# GPS-speed.net
KiCad netlist of a schematic drawn in Altium Designer
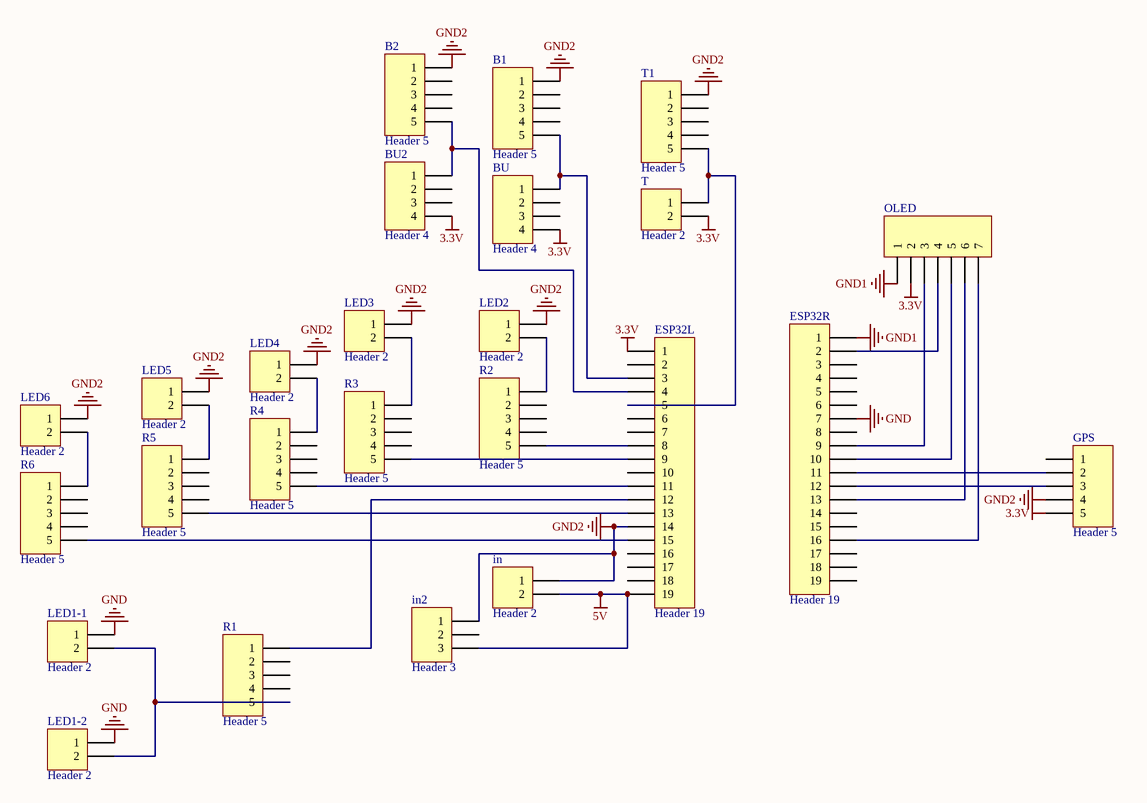
[diagram p0: GPS-speed.SchDoc]

(export (version "E")
  (design (tool "Eeschema 10.0.6"))
  (components
    (comp (ref "B1")
      (value "Header 5")
      (footprint "HDR1X5")
      (description "Header, 5-Pin")
      (fields (field (name "PUBLISHER") "Altium Limited"))
      (libsource (lib "Miscellaneous Connectors") (part "Header 5"))
    )
    (comp (ref "B2")
      (value "Header 5")
      (footprint "HDR1X5")
      (description "Header, 5-Pin")
      (fields (field (name "PUBLISHER") "Altium Limited"))
      (libsource (lib "Miscellaneous Connectors") (part "Header 5"))
    )
    (comp (ref "BU")
      (value "Header 4")
      (footprint "HDR1X4")
      (description "Header, 4-Pin")
      (fields (field (name "PUBLISHER") "Altium Limited"))
      (libsource (lib "Miscellaneous Connectors") (part "Header 4"))
    )
    (comp (ref "BU2")
      (value "Header 4")
      (footprint "HDR1X4")
      (description "Header, 4-Pin")
      (fields (field (name "PUBLISHER") "Altium Limited"))
      (libsource (lib "Miscellaneous Connectors") (part "Header 4"))
    )
    (comp (ref "ESP32L")
      (value "Header 19")
      (footprint "HDR1X19")
      (description "Header, 19-Pin")
      (fields (field (name "PUBLISHER") "Altium Limited"))
      (libsource (lib "") (part "Header 19_1"))
    )
    (comp (ref "ESP32R")
      (value "Header 19")
      (footprint "HDR1X19")
      (description "Header, 19-Pin")
      (fields (field (name "PUBLISHER") "Altium Limited"))
      (libsource (lib "Miscellaneous Connectors") (part "Header 19"))
    )
    (comp (ref "GPS")
      (value "Header 5")
      (footprint "HDR1X5")
      (description "Header, 5-Pin")
      (fields (field (name "PUBLISHER") "Altium Limited"))
      (libsource (lib "") (part "Header 5_1"))
    )
    (comp (ref "in")
      (value "Header 2")
      (footprint "HDR1X2")
      (description "Header, 2-Pin")
      (fields (field (name "PUBLISHER") "Altium Limited"))
      (libsource (lib "Miscellaneous Connectors") (part "Header 2"))
    )
    (comp (ref "in2")
      (value "Header 3")
      (footprint "HDR1X3")
      (description "Header, 3-Pin")
      (fields (field (name "PUBLISHER") "Altium Limited"))
      (libsource (lib "Miscellaneous Connectors") (part "Header 3"))
    )
    (comp (ref "LED1-1")
      (value "Header 2")
      (footprint "HDR1X2")
      (description "Header, 2-Pin")
      (fields (field (name "PUBLISHER") "Altium Limited"))
      (libsource (lib "Miscellaneous Connectors") (part "Header 2"))
    )
    (comp (ref "LED1-2")
      (value "Header 2")
      (footprint "HDR1X2")
      (description "Header, 2-Pin")
      (fields (field (name "PUBLISHER") "Altium Limited"))
      (libsource (lib "Miscellaneous Connectors") (part "Header 2"))
    )
    (comp (ref "LED2")
      (value "Header 2")
      (footprint "HDR1X2")
      (description "Header, 2-Pin")
      (fields (field (name "PUBLISHER") "Altium Limited"))
      (libsource (lib "Miscellaneous Connectors") (part "Header 2"))
    )
    (comp (ref "LED3")
      (value "Header 2")
      (footprint "HDR1X2")
      (description "Header, 2-Pin")
      (fields (field (name "PUBLISHER") "Altium Limited"))
      (libsource (lib "Miscellaneous Connectors") (part "Header 2"))
    )
    (comp (ref "LED4")
      (value "Header 2")
      (footprint "HDR1X2")
      (description "Header, 2-Pin")
      (fields (field (name "PUBLISHER") "Altium Limited"))
      (libsource (lib "Miscellaneous Connectors") (part "Header 2"))
    )
    (comp (ref "LED5")
      (value "Header 2")
      (footprint "HDR1X2")
      (description "Header, 2-Pin")
      (fields (field (name "PUBLISHER") "Altium Limited"))
      (libsource (lib "Miscellaneous Connectors") (part "Header 2"))
    )
    (comp (ref "LED6")
      (value "Header 2")
      (footprint "HDR1X2")
      (description "Header, 2-Pin")
      (fields (field (name "PUBLISHER") "Altium Limited"))
      (libsource (lib "Miscellaneous Connectors") (part "Header 2"))
    )
    (comp (ref "OLED")
      (value "Header 7")
      (footprint "HDR1X7")
      (description "Header, 7-Pin")
      (fields (field (name "PUBLISHER") "Altium Limited"))
      (libsource (lib "Miscellaneous Connectors") (part "Header 7"))
    )
    (comp (ref "R1")
      (value "Header 5")
      (footprint "HDR1X5")
      (description "Header, 5-Pin")
      (fields (field (name "PUBLISHER") "Altium Limited"))
      (libsource (lib "Miscellaneous Connectors") (part "Header 5"))
    )
    (comp (ref "R2")
      (value "Header 5")
      (footprint "HDR1X5")
      (description "Header, 5-Pin")
      (fields (field (name "PUBLISHER") "Altium Limited"))
      (libsource (lib "Miscellaneous Connectors") (part "Header 5"))
    )
    (comp (ref "R3")
      (value "Header 5")
      (footprint "HDR1X5")
      (description "Header, 5-Pin")
      (fields (field (name "PUBLISHER") "Altium Limited"))
      (libsource (lib "Miscellaneous Connectors") (part "Header 5"))
    )
    (comp (ref "R4")
      (value "Header 5")
      (footprint "HDR1X5")
      (description "Header, 5-Pin")
      (fields (field (name "PUBLISHER") "Altium Limited"))
      (libsource (lib "Miscellaneous Connectors") (part "Header 5"))
    )
    (comp (ref "R5")
      (value "Header 5")
      (footprint "HDR1X5")
      (description "Header, 5-Pin")
      (fields (field (name "PUBLISHER") "Altium Limited"))
      (libsource (lib "Miscellaneous Connectors") (part "Header 5"))
    )
    (comp (ref "R6")
      (value "Header 5")
      (footprint "HDR1X5")
      (description "Header, 5-Pin")
      (fields (field (name "PUBLISHER") "Altium Limited"))
      (libsource (lib "Miscellaneous Connectors") (part "Header 5"))
    )
    (comp (ref "T")
      (value "Header 2")
      (footprint "HDR1X2")
      (description "Header, 2-Pin")
      (fields (field (name "PUBLISHER") "Altium Limited"))
      (libsource (lib "Miscellaneous Connectors") (part "Header 2"))
    )
    (comp (ref "T1")
      (value "Header 5")
      (footprint "HDR1X5")
      (description "Header, 5-Pin")
      (fields (field (name "PUBLISHER") "Altium Limited"))
      (libsource (lib "Miscellaneous Connectors") (part "Header 5"))
    )
  )
  (nets
    (net (code "1") (name "3.3V") (class "Default")
      (node (ref "BU") (pin "4") (pinfunction "4_4") (pintype "passive"))
      (node (ref "BU2") (pin "4") (pinfunction "4_4") (pintype "passive"))
      (node (ref "ESP32L") (pin "1") (pinfunction "1_1") (pintype "passive"))
      (node (ref "GPS") (pin "5") (pinfunction "5_5") (pintype "passive"))
      (node (ref "OLED") (pin "2") (pinfunction "2_2") (pintype "passive"))
      (node (ref "T") (pin "2") (pinfunction "2_2") (pintype "passive"))
    )
    (net (code "2") (name "5V") (class "Default")
      (node (ref "ESP32L") (pin "19") (pinfunction "19_19") (pintype "passive"))
      (node (ref "in") (pin "2") (pinfunction "2_2") (pintype "passive"))
      (node (ref "in2") (pin "3") (pinfunction "3_3") (pintype "passive"))
    )
    (net (code "3") (name "GND") (class "Default")
      (node (ref "ESP32R") (pin "7") (pinfunction "7_7") (pintype "passive"))
      (node (ref "LED1-1") (pin "1") (pinfunction "1_1") (pintype "passive"))
      (node (ref "LED1-2") (pin "1") (pinfunction "1_1") (pintype "passive"))
    )
    (net (code "4") (name "GND1") (class "Default")
      (node (ref "ESP32R") (pin "1") (pinfunction "1_1") (pintype "passive"))
      (node (ref "OLED") (pin "1") (pinfunction "1_1") (pintype "passive"))
    )
    (net (code "5") (name "GND2") (class "Default")
      (node (ref "B1") (pin "1") (pinfunction "1_1") (pintype "passive"))
      (node (ref "B2") (pin "1") (pinfunction "1_1") (pintype "passive"))
      (node (ref "ESP32L") (pin "14") (pinfunction "14_14") (pintype "passive"))
      (node (ref "GPS") (pin "4") (pinfunction "4_4") (pintype "passive"))
      (node (ref "LED2") (pin "1") (pinfunction "1_1") (pintype "passive"))
      (node (ref "LED3") (pin "1") (pinfunction "1_1") (pintype "passive"))
      (node (ref "LED4") (pin "1") (pinfunction "1_1") (pintype "passive"))
      (node (ref "LED5") (pin "1") (pinfunction "1_1") (pintype "passive"))
      (node (ref "LED6") (pin "1") (pinfunction "1_1") (pintype "passive"))
      (node (ref "T1") (pin "1") (pinfunction "1_1") (pintype "passive"))
      (node (ref "in") (pin "1") (pinfunction "1_1") (pintype "passive"))
      (node (ref "in2") (pin "1") (pinfunction "1_1") (pintype "passive"))
    )
    (net (code "6") (name "Net-(B1-Pad5)") (class "Default")
      (node (ref "B1") (pin "5") (pinfunction "5_5") (pintype "passive"))
      (node (ref "BU") (pin "1") (pinfunction "1_1") (pintype "passive"))
      (node (ref "ESP32L") (pin "3") (pinfunction "3_3") (pintype "passive"))
    )
    (net (code "7") (name "Net-(B2-Pad5)") (class "Default")
      (node (ref "B2") (pin "5") (pinfunction "5_5") (pintype "passive"))
      (node (ref "BU2") (pin "1") (pinfunction "1_1") (pintype "passive"))
      (node (ref "ESP32L") (pin "4") (pinfunction "4_4") (pintype "passive"))
    )
    (net (code "8") (name "Net-(ESP32L-Pad5)") (class "Default")
      (node (ref "ESP32L") (pin "5") (pinfunction "5_5") (pintype "passive"))
      (node (ref "T") (pin "1") (pinfunction "1_1") (pintype "passive"))
      (node (ref "T1") (pin "5") (pinfunction "5_5") (pintype "passive"))
    )
    (net (code "9") (name "Net-(ESP32L-Pad8)") (class "Default")
      (node (ref "ESP32L") (pin "8") (pinfunction "8_8") (pintype "passive"))
      (node (ref "R2") (pin "5") (pinfunction "5_5") (pintype "passive"))
    )
    (net (code "10") (name "Net-(ESP32L-Pad9)") (class "Default")
      (node (ref "ESP32L") (pin "9") (pinfunction "9_9") (pintype "passive"))
      (node (ref "R3") (pin "5") (pinfunction "5_5") (pintype "passive"))
    )
    (net (code "11") (name "Net-(ESP32L-Pad11)") (class "Default")
      (node (ref "ESP32L") (pin "11") (pinfunction "11_11") (pintype "passive"))
      (node (ref "R4") (pin "5") (pinfunction "5_5") (pintype "passive"))
    )
    (net (code "12") (name "Net-(ESP32L-Pad12)") (class "Default")
      (node (ref "ESP32L") (pin "12") (pinfunction "12_12") (pintype "passive"))
      (node (ref "R1") (pin "1") (pinfunction "1_1") (pintype "passive"))
    )
    (net (code "13") (name "Net-(ESP32L-Pad13)") (class "Default")
      (node (ref "ESP32L") (pin "13") (pinfunction "13_13") (pintype "passive"))
      (node (ref "R5") (pin "5") (pinfunction "5_5") (pintype "passive"))
    )
    (net (code "14") (name "Net-(ESP32L-Pad15)") (class "Default")
      (node (ref "ESP32L") (pin "15") (pinfunction "15_15") (pintype "passive"))
      (node (ref "R6") (pin "5") (pinfunction "5_5") (pintype "passive"))
    )
    (net (code "15") (name "Net-(ESP32R-Pad2)") (class "Default")
      (node (ref "ESP32R") (pin "2") (pinfunction "2_2") (pintype "passive"))
      (node (ref "OLED") (pin "4") (pinfunction "4_4") (pintype "passive"))
    )
    (net (code "16") (name "Net-(ESP32R-Pad9)") (class "Default")
      (node (ref "ESP32R") (pin "9") (pinfunction "9_9") (pintype "passive"))
      (node (ref "OLED") (pin "3") (pinfunction "3_3") (pintype "passive"))
    )
    (net (code "17") (name "Net-(ESP32R-Pad10)") (class "Default")
      (node (ref "ESP32R") (pin "10") (pinfunction "10_10") (pintype "passive"))
      (node (ref "OLED") (pin "5") (pinfunction "5_5") (pintype "passive"))
    )
    (net (code "18") (name "Net-(ESP32R-Pad11)") (class "Default")
      (node (ref "ESP32R") (pin "11") (pinfunction "11_11") (pintype "passive"))
      (node (ref "GPS") (pin "2") (pinfunction "2_2") (pintype "passive"))
    )
    (net (code "19") (name "Net-(ESP32R-Pad12)") (class "Default")
      (node (ref "ESP32R") (pin "12") (pinfunction "12_12") (pintype "passive"))
      (node (ref "GPS") (pin "3") (pinfunction "3_3") (pintype "passive"))
    )
    (net (code "20") (name "Net-(ESP32R-Pad13)") (class "Default")
      (node (ref "ESP32R") (pin "13") (pinfunction "13_13") (pintype "passive"))
      (node (ref "OLED") (pin "6") (pinfunction "6_6") (pintype "passive"))
    )
    (net (code "21") (name "Net-(ESP32R-Pad16)") (class "Default")
      (node (ref "ESP32R") (pin "16") (pinfunction "16_16") (pintype "passive"))
      (node (ref "OLED") (pin "7") (pinfunction "7_7") (pintype "passive"))
    )
    (net (code "22") (name "Net-(LED1-1-Pad2)") (class "Default")
      (node (ref "LED1-1") (pin "2") (pinfunction "2_2") (pintype "passive"))
      (node (ref "LED1-2") (pin "2") (pinfunction "2_2") (pintype "passive"))
      (node (ref "R1") (pin "5") (pinfunction "5_5") (pintype "passive"))
    )
    (net (code "23") (name "Net-(LED2-Pad2)") (class "Default")
      (node (ref "LED2") (pin "2") (pinfunction "2_2") (pintype "passive"))
      (node (ref "R2") (pin "1") (pinfunction "1_1") (pintype "passive"))
    )
    (net (code "24") (name "Net-(LED3-Pad2)") (class "Default")
      (node (ref "LED3") (pin "2") (pinfunction "2_2") (pintype "passive"))
      (node (ref "R3") (pin "1") (pinfunction "1_1") (pintype "passive"))
    )
    (net (code "25") (name "Net-(LED4-Pad2)") (class "Default")
      (node (ref "LED4") (pin "2") (pinfunction "2_2") (pintype "passive"))
      (node (ref "R4") (pin "1") (pinfunction "1_1") (pintype "passive"))
    )
    (net (code "26") (name "Net-(LED5-Pad2)") (class "Default")
      (node (ref "LED5") (pin "2") (pinfunction "2_2") (pintype "passive"))
      (node (ref "R5") (pin "1") (pinfunction "1_1") (pintype "passive"))
    )
    (net (code "27") (name "Net-(LED6-Pad2)") (class "Default")
      (node (ref "LED6") (pin "2") (pinfunction "2_2") (pintype "passive"))
      (node (ref "R6") (pin "1") (pinfunction "1_1") (pintype "passive"))
    )
    (net (code "28") (name "unconnected-(B1-Pad2)") (class "Default")
      (node (ref "B1") (pin "2") (pinfunction "2_2") (pintype "passive"))
    )
    (net (code "29") (name "unconnected-(B1-Pad3)") (class "Default")
      (node (ref "B1") (pin "3") (pinfunction "3_3") (pintype "passive"))
    )
    (net (code "30") (name "unconnected-(B1-Pad4)") (class "Default")
      (node (ref "B1") (pin "4") (pinfunction "4_4") (pintype "passive"))
    )
    (net (code "31") (name "unconnected-(B2-Pad2)") (class "Default")
      (node (ref "B2") (pin "2") (pinfunction "2_2") (pintype "passive"))
    )
    (net (code "32") (name "unconnected-(B2-Pad3)") (class "Default")
      (node (ref "B2") (pin "3") (pinfunction "3_3") (pintype "passive"))
    )
    (net (code "33") (name "unconnected-(B2-Pad4)") (class "Default")
      (node (ref "B2") (pin "4") (pinfunction "4_4") (pintype "passive"))
    )
    (net (code "34") (name "unconnected-(BU-Pad2)") (class "Default")
      (node (ref "BU") (pin "2") (pinfunction "2_2") (pintype "passive"))
    )
    (net (code "35") (name "unconnected-(BU-Pad3)") (class "Default")
      (node (ref "BU") (pin "3") (pinfunction "3_3") (pintype "passive"))
    )
    (net (code "36") (name "unconnected-(BU2-Pad2)") (class "Default")
      (node (ref "BU2") (pin "2") (pinfunction "2_2") (pintype "passive"))
    )
    (net (code "37") (name "unconnected-(BU2-Pad3)") (class "Default")
      (node (ref "BU2") (pin "3") (pinfunction "3_3") (pintype "passive"))
    )
    (net (code "38") (name "unconnected-(ESP32L-Pad2)") (class "Default")
      (node (ref "ESP32L") (pin "2") (pinfunction "2_2") (pintype "passive"))
    )
    (net (code "39") (name "unconnected-(ESP32L-Pad6)") (class "Default")
      (node (ref "ESP32L") (pin "6") (pinfunction "6_6") (pintype "passive"))
    )
    (net (code "40") (name "unconnected-(ESP32L-Pad7)") (class "Default")
      (node (ref "ESP32L") (pin "7") (pinfunction "7_7") (pintype "passive"))
    )
    (net (code "41") (name "unconnected-(ESP32L-Pad10)") (class "Default")
      (node (ref "ESP32L") (pin "10") (pinfunction "10_10") (pintype "passive"))
    )
    (net (code "42") (name "unconnected-(ESP32L-Pad16)") (class "Default")
      (node (ref "ESP32L") (pin "16") (pinfunction "16_16") (pintype "passive"))
    )
    (net (code "43") (name "unconnected-(ESP32L-Pad17)") (class "Default")
      (node (ref "ESP32L") (pin "17") (pinfunction "17_17") (pintype "passive"))
    )
    (net (code "44") (name "unconnected-(ESP32L-Pad18)") (class "Default")
      (node (ref "ESP32L") (pin "18") (pinfunction "18_18") (pintype "passive"))
    )
    (net (code "45") (name "unconnected-(ESP32R-Pad3)") (class "Default")
      (node (ref "ESP32R") (pin "3") (pinfunction "3_3") (pintype "passive"))
    )
    (net (code "46") (name "unconnected-(ESP32R-Pad4)") (class "Default")
      (node (ref "ESP32R") (pin "4") (pinfunction "4_4") (pintype "passive"))
    )
    (net (code "47") (name "unconnected-(ESP32R-Pad5)") (class "Default")
      (node (ref "ESP32R") (pin "5") (pinfunction "5_5") (pintype "passive"))
    )
    (net (code "48") (name "unconnected-(ESP32R-Pad6)") (class "Default")
      (node (ref "ESP32R") (pin "6") (pinfunction "6_6") (pintype "passive"))
    )
    (net (code "49") (name "unconnected-(ESP32R-Pad8)") (class "Default")
      (node (ref "ESP32R") (pin "8") (pinfunction "8_8") (pintype "passive"))
    )
    (net (code "50") (name "unconnected-(ESP32R-Pad14)") (class "Default")
      (node (ref "ESP32R") (pin "14") (pinfunction "14_14") (pintype "passive"))
    )
    (net (code "51") (name "unconnected-(ESP32R-Pad15)") (class "Default")
      (node (ref "ESP32R") (pin "15") (pinfunction "15_15") (pintype "passive"))
    )
    (net (code "52") (name "unconnected-(ESP32R-Pad17)") (class "Default")
      (node (ref "ESP32R") (pin "17") (pinfunction "17_17") (pintype "passive"))
    )
    (net (code "53") (name "unconnected-(ESP32R-Pad18)") (class "Default")
      (node (ref "ESP32R") (pin "18") (pinfunction "18_18") (pintype "passive"))
    )
    (net (code "54") (name "unconnected-(ESP32R-Pad19)") (class "Default")
      (node (ref "ESP32R") (pin "19") (pinfunction "19_19") (pintype "passive"))
    )
    (net (code "55") (name "unconnected-(GPS-Pad1)") (class "Default")
      (node (ref "GPS") (pin "1") (pinfunction "1_1") (pintype "passive"))
    )
    (net (code "56") (name "unconnected-(R1-Pad2)") (class "Default")
      (node (ref "R1") (pin "2") (pinfunction "2_2") (pintype "passive"))
    )
    (net (code "57") (name "unconnected-(R1-Pad3)") (class "Default")
      (node (ref "R1") (pin "3") (pinfunction "3_3") (pintype "passive"))
    )
    (net (code "58") (name "unconnected-(R1-Pad4)") (class "Default")
      (node (ref "R1") (pin "4") (pinfunction "4_4") (pintype "passive"))
    )
    (net (code "59") (name "unconnected-(R2-Pad2)") (class "Default")
      (node (ref "R2") (pin "2") (pinfunction "2_2") (pintype "passive"))
    )
    (net (code "60") (name "unconnected-(R2-Pad3)") (class "Default")
      (node (ref "R2") (pin "3") (pinfunction "3_3") (pintype "passive"))
    )
    (net (code "61") (name "unconnected-(R2-Pad4)") (class "Default")
      (node (ref "R2") (pin "4") (pinfunction "4_4") (pintype "passive"))
    )
    (net (code "62") (name "unconnected-(R3-Pad2)") (class "Default")
      (node (ref "R3") (pin "2") (pinfunction "2_2") (pintype "passive"))
    )
    (net (code "63") (name "unconnected-(R3-Pad3)") (class "Default")
      (node (ref "R3") (pin "3") (pinfunction "3_3") (pintype "passive"))
    )
    (net (code "64") (name "unconnected-(R3-Pad4)") (class "Default")
      (node (ref "R3") (pin "4") (pinfunction "4_4") (pintype "passive"))
    )
    (net (code "65") (name "unconnected-(R4-Pad2)") (class "Default")
      (node (ref "R4") (pin "2") (pinfunction "2_2") (pintype "passive"))
    )
    (net (code "66") (name "unconnected-(R4-Pad3)") (class "Default")
      (node (ref "R4") (pin "3") (pinfunction "3_3") (pintype "passive"))
    )
    (net (code "67") (name "unconnected-(R4-Pad4)") (class "Default")
      (node (ref "R4") (pin "4") (pinfunction "4_4") (pintype "passive"))
    )
    (net (code "68") (name "unconnected-(R5-Pad2)") (class "Default")
      (node (ref "R5") (pin "2") (pinfunction "2_2") (pintype "passive"))
    )
    (net (code "69") (name "unconnected-(R5-Pad3)") (class "Default")
      (node (ref "R5") (pin "3") (pinfunction "3_3") (pintype "passive"))
    )
    (net (code "70") (name "unconnected-(R5-Pad4)") (class "Default")
      (node (ref "R5") (pin "4") (pinfunction "4_4") (pintype "passive"))
    )
    (net (code "71") (name "unconnected-(R6-Pad2)") (class "Default")
      (node (ref "R6") (pin "2") (pinfunction "2_2") (pintype "passive"))
    )
    (net (code "72") (name "unconnected-(R6-Pad3)") (class "Default")
      (node (ref "R6") (pin "3") (pinfunction "3_3") (pintype "passive"))
    )
    (net (code "73") (name "unconnected-(R6-Pad4)") (class "Default")
      (node (ref "R6") (pin "4") (pinfunction "4_4") (pintype "passive"))
    )
    (net (code "74") (name "unconnected-(T1-Pad2)") (class "Default")
      (node (ref "T1") (pin "2") (pinfunction "2_2") (pintype "passive"))
    )
    (net (code "75") (name "unconnected-(T1-Pad3)") (class "Default")
      (node (ref "T1") (pin "3") (pinfunction "3_3") (pintype "passive"))
    )
    (net (code "76") (name "unconnected-(T1-Pad4)") (class "Default")
      (node (ref "T1") (pin "4") (pinfunction "4_4") (pintype "passive"))
    )
    (net (code "77") (name "unconnected-(in2-Pad2)") (class "Default")
      (node (ref "in2") (pin "2") (pinfunction "2_2") (pintype "passive"))
    )
  )
)
